# SCH_TempBoard-copy-copy_2024-06-04.net
KiCad netlist of a schematic drawn in EasyEDA
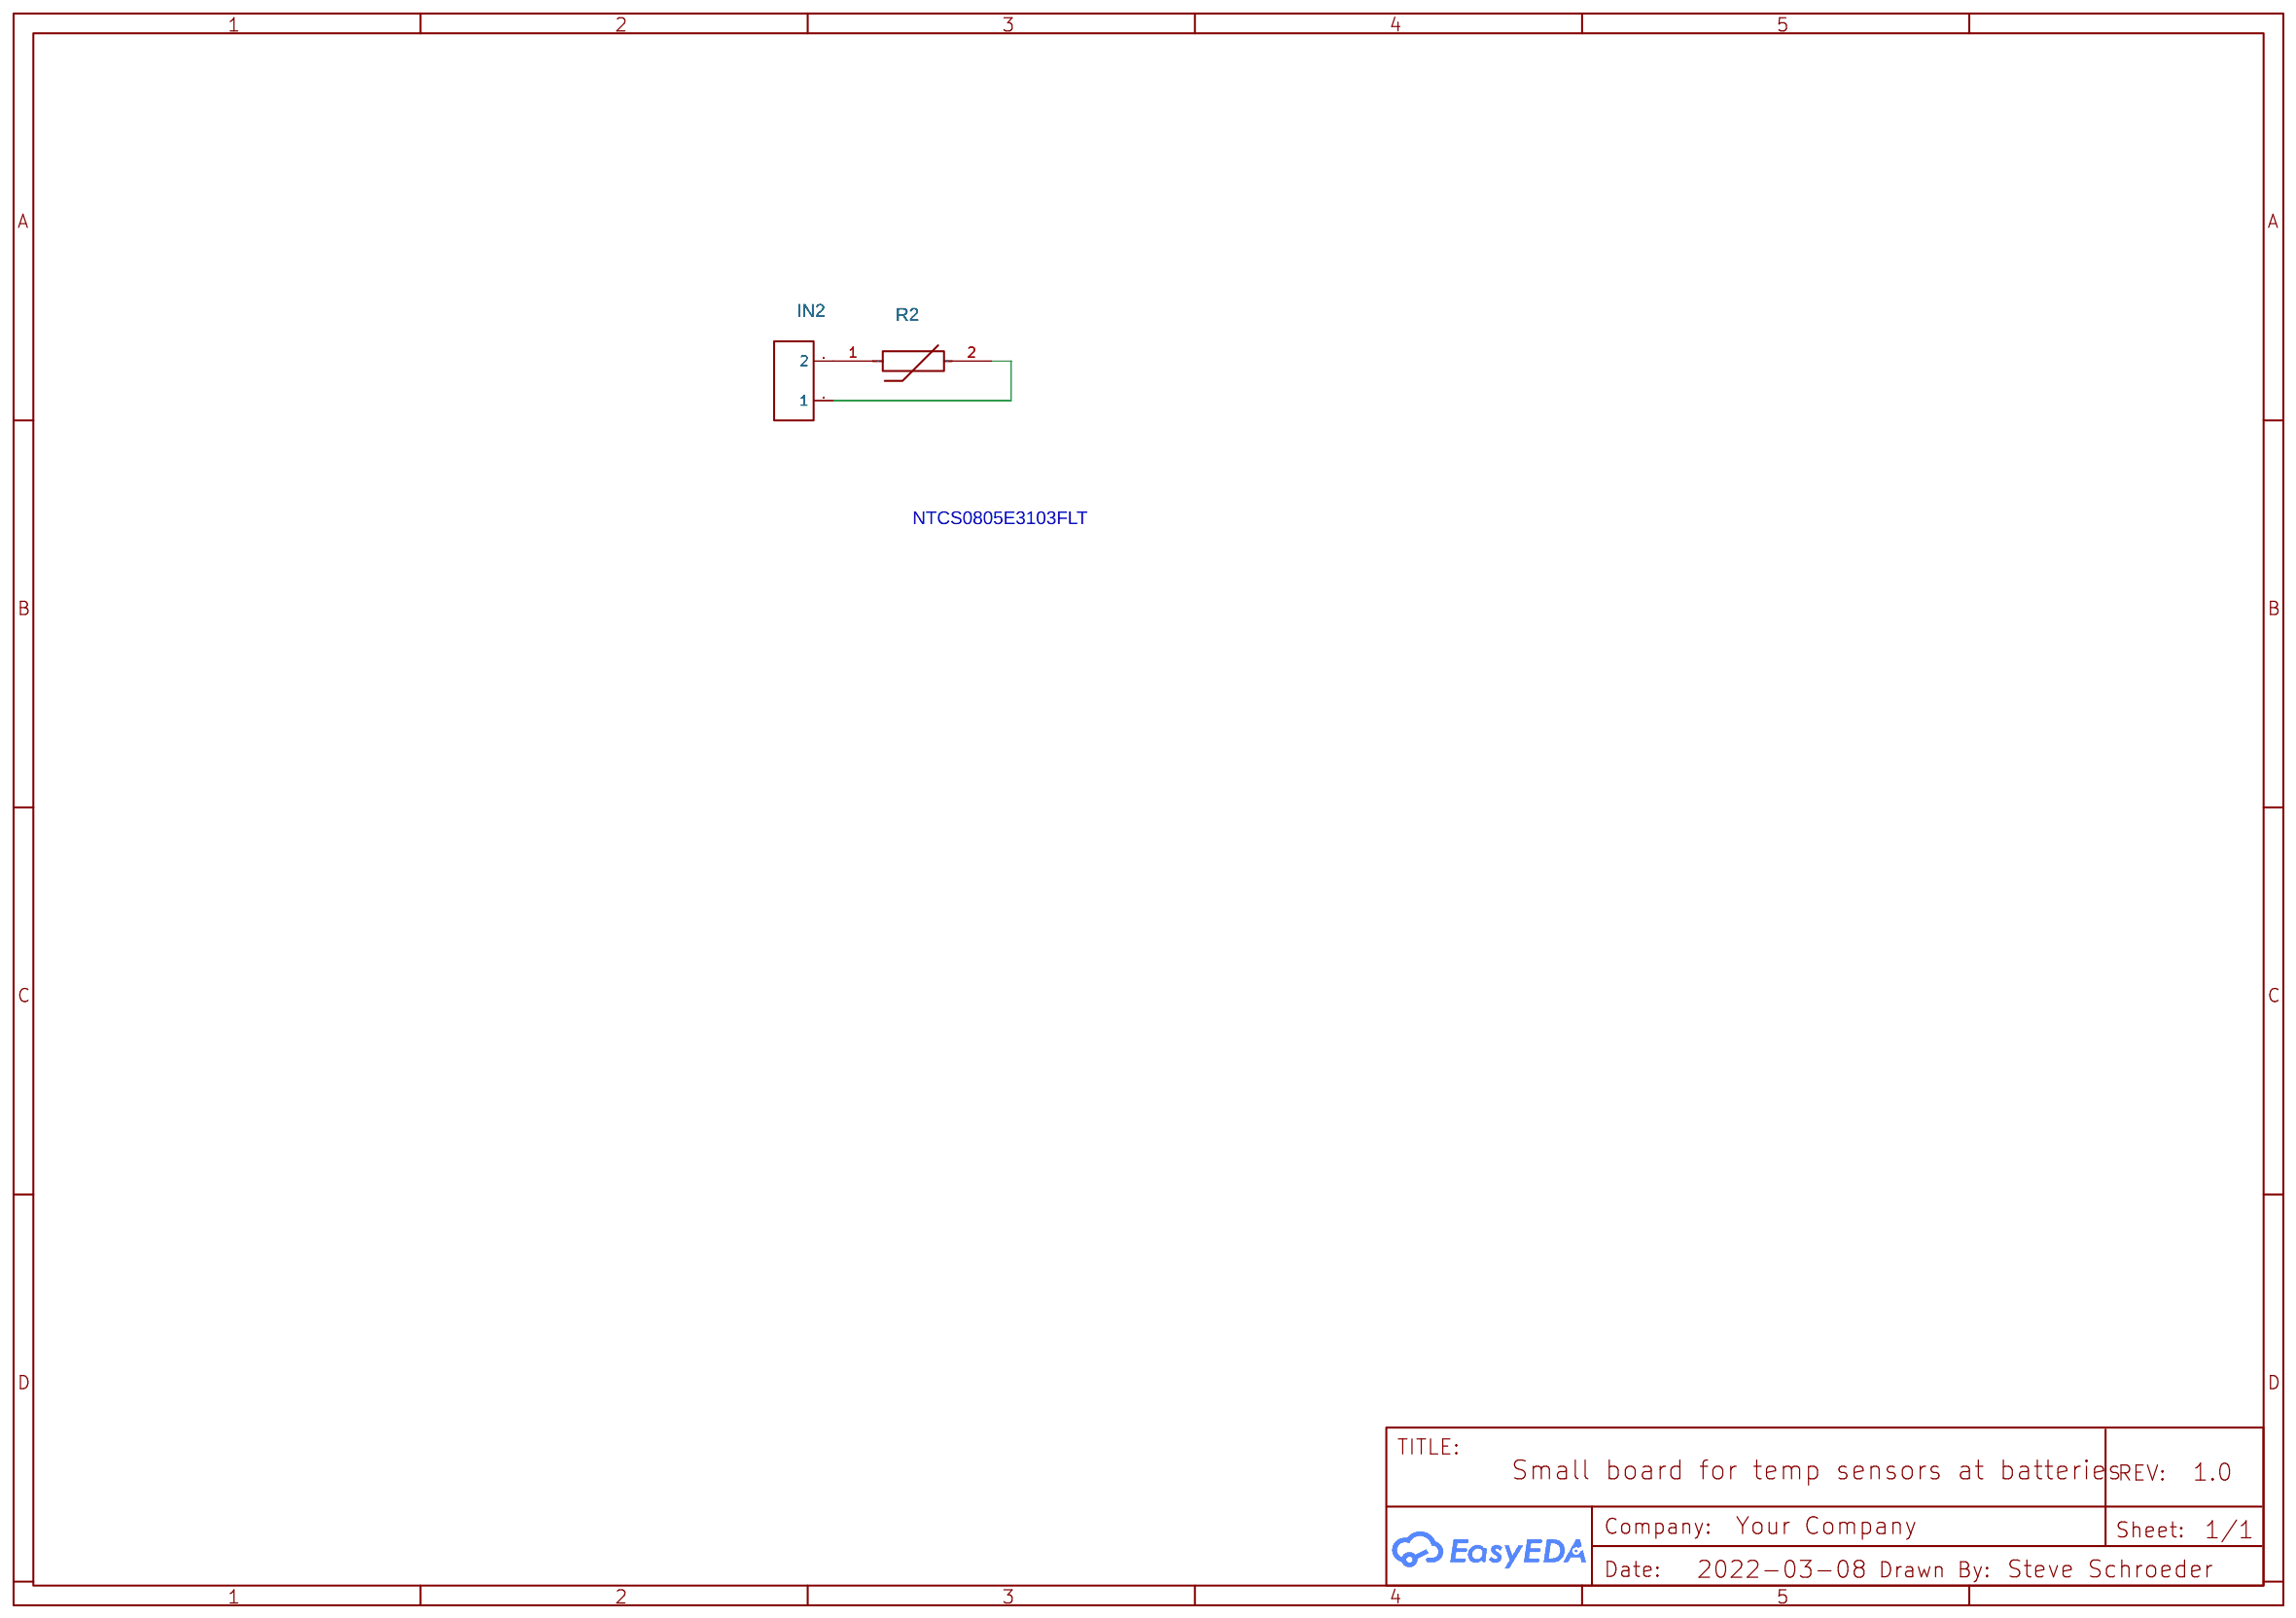
[diagram p0: schematic sheet]

(export (version "E")
  (design (tool "Eeschema 10.0.6"))
  (components
    (comp (ref "IN2")
      (value "Header-Male-2.54_1x2")
      (fields (field (name "Manufacturer Part") "826629-2") (field (name "Manufacturer") "TE Connectivity"))
      (libsource (lib "") (part "Header-Male-2.54_1x2"))
    )
    (comp (ref "R2")
      (value "NTCS0805E3103JHT")
      (fields (field (name "Manufacturer") "Vishay Intertech"))
      (libsource (lib "") (part "NTCS0805E3103JHT"))
    )
  )
  (nets
    (net (code "1") (name "Net-(IN2-Pad1)") (class "Default")
      (node (ref "IN2") (pin "1") (pinfunction "1_1") (pintype "unspecified"))
      (node (ref "R2") (pin "2") (pinfunction "2_2") (pintype "unspecified"))
    )
    (net (code "2") (name "Net-(IN2-Pad2)") (class "Default")
      (node (ref "IN2") (pin "2") (pinfunction "2_2") (pintype "unspecified"))
      (node (ref "R2") (pin "1") (pinfunction "1_1") (pintype "unspecified"))
    )
  )
)
